# Driver_Board.net
KiCad netlist of a schematic drawn in EAGLE
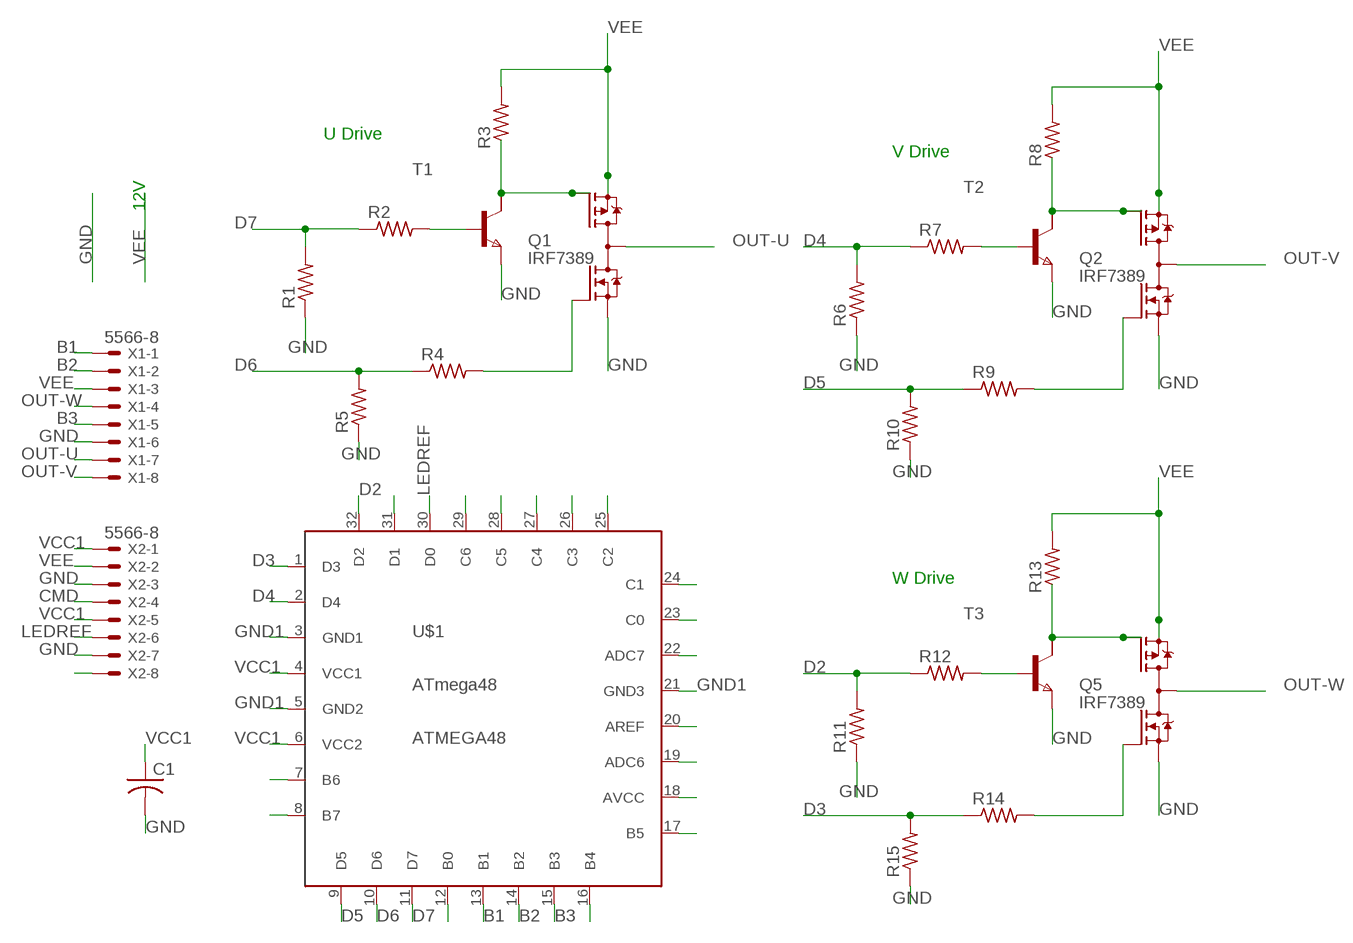
[diagram p0: schematic, sheet 1]

(export (version "E")
  (design (tool "Eeschema 10.0.6"))
  (components
    (comp (ref "C1")
      (value "C-USC1206")
      (footprint "eagle-import:C1206")
      (libsource (lib "eagle-import") (part "C-USC1206"))
    )
    (comp (ref "Q1")
      (value "IRF7389")
      (footprint "eagle-import:SO08-IRF")
      (libsource (lib "eagle-import") (part "IRF7389"))
    )
    (comp (ref "Q2")
      (value "IRF7389")
      (footprint "eagle-import:SO08-IRF")
      (libsource (lib "eagle-import") (part "IRF7389"))
    )
    (comp (ref "Q5")
      (value "IRF7389")
      (footprint "eagle-import:SO08-IRF")
      (libsource (lib "eagle-import") (part "IRF7389"))
    )
    (comp (ref "R1")
      (value "R-US_R1206")
      (footprint "eagle-import:R1206")
      (libsource (lib "eagle-import") (part "R-US_R1206"))
    )
    (comp (ref "R2")
      (value "R-US_R1206")
      (footprint "eagle-import:R1206")
      (libsource (lib "eagle-import") (part "R-US_R1206"))
    )
    (comp (ref "R3")
      (value "R-US_R1206")
      (footprint "eagle-import:R1206")
      (libsource (lib "eagle-import") (part "R-US_R1206"))
    )
    (comp (ref "R4")
      (value "R-US_R1206")
      (footprint "eagle-import:R1206")
      (libsource (lib "eagle-import") (part "R-US_R1206"))
    )
    (comp (ref "R5")
      (value "R-US_R1206")
      (footprint "eagle-import:R1206")
      (libsource (lib "eagle-import") (part "R-US_R1206"))
    )
    (comp (ref "R6")
      (value "R-US_R1206")
      (footprint "eagle-import:R1206")
      (libsource (lib "eagle-import") (part "R-US_R1206"))
    )
    (comp (ref "R7")
      (value "R-US_R1206")
      (footprint "eagle-import:R1206")
      (libsource (lib "eagle-import") (part "R-US_R1206"))
    )
    (comp (ref "R8")
      (value "R-US_R1206")
      (footprint "eagle-import:R1206")
      (libsource (lib "eagle-import") (part "R-US_R1206"))
    )
    (comp (ref "R9")
      (value "R-US_R1206")
      (footprint "eagle-import:R1206")
      (libsource (lib "eagle-import") (part "R-US_R1206"))
    )
    (comp (ref "R10")
      (value "R-US_R1206")
      (footprint "eagle-import:R1206")
      (libsource (lib "eagle-import") (part "R-US_R1206"))
    )
    (comp (ref "R11")
      (value "R-US_R1206")
      (footprint "eagle-import:R1206")
      (libsource (lib "eagle-import") (part "R-US_R1206"))
    )
    (comp (ref "R12")
      (value "R-US_R1206")
      (footprint "eagle-import:R1206")
      (libsource (lib "eagle-import") (part "R-US_R1206"))
    )
    (comp (ref "R13")
      (value "R-US_R1206")
      (footprint "eagle-import:R1206")
      (libsource (lib "eagle-import") (part "R-US_R1206"))
    )
    (comp (ref "R14")
      (value "R-US_R1206")
      (footprint "eagle-import:R1206")
      (libsource (lib "eagle-import") (part "R-US_R1206"))
    )
    (comp (ref "R15")
      (value "R-US_R1206")
      (footprint "eagle-import:R1206")
      (libsource (lib "eagle-import") (part "R-US_R1206"))
    )
    (comp (ref "T1")
      (value "NPNSOT223")
      (footprint "eagle-import:SOT223")
      (fields (field (name "MPN") "DJT4031N-13"))
      (libsource (lib "eagle-import") (part "NPNSOT223"))
    )
    (comp (ref "T2")
      (value "NPNSOT223")
      (footprint "eagle-import:SOT223")
      (fields (field (name "MPN") "DJT4031N-13"))
      (libsource (lib "eagle-import") (part "NPNSOT223"))
    )
    (comp (ref "T3")
      (value "NPNSOT223")
      (footprint "eagle-import:SOT223")
      (fields (field (name "MPN") "DJT4031N-13"))
      (libsource (lib "eagle-import") (part "NPNSOT223"))
    )
    (comp (ref "U$1")
      (value "ATMEGA48")
      (footprint "eagle-import:ATMEGA48")
      (libsource (lib "eagle-import") (part "ATMEGA48"))
    )
    (comp (ref "X1")
      (value "5566-8")
      (footprint "eagle-import:5566-8")
      (libsource (lib "eagle-import") (part "5566-8"))
    )
    (comp (ref "X2")
      (value "5566-8")
      (footprint "eagle-import:5566-8")
      (libsource (lib "eagle-import") (part "5566-8"))
    )
  )
  (nets
    (net (code "1") (name "/B1") (class "Default")
      (node (ref "U$1") (pin "13") (pinfunction "B1_13") (pintype "bidirectional"))
      (node (ref "X1") (pin "1") (pinfunction "S_1") (pintype "passive"))
    )
    (net (code "2") (name "/B2") (class "Default")
      (node (ref "U$1") (pin "14") (pinfunction "B2_14") (pintype "bidirectional"))
      (node (ref "X1") (pin "2") (pinfunction "S_2") (pintype "passive"))
    )
    (net (code "3") (name "/B3") (class "Default")
      (node (ref "U$1") (pin "15") (pinfunction "B3_15") (pintype "bidirectional"))
      (node (ref "X1") (pin "5") (pinfunction "S_5") (pintype "passive"))
    )
    (net (code "4") (name "/CMD") (class "Default")
      (node (ref "X2") (pin "4") (pinfunction "S_4") (pintype "passive"))
    )
    (net (code "5") (name "/D2") (class "Default")
      (node (ref "R11") (pin "2") (pinfunction "2_2") (pintype "passive"))
      (node (ref "R12") (pin "1") (pinfunction "1_1") (pintype "passive"))
      (node (ref "U$1") (pin "32") (pinfunction "D2_32") (pintype "bidirectional"))
    )
    (net (code "6") (name "/D3") (class "Default")
      (node (ref "R14") (pin "1") (pinfunction "1_1") (pintype "passive"))
      (node (ref "R15") (pin "2") (pinfunction "2_2") (pintype "passive"))
      (node (ref "U$1") (pin "1") (pinfunction "D3_1") (pintype "bidirectional"))
    )
    (net (code "7") (name "/D4") (class "Default")
      (node (ref "R6") (pin "2") (pinfunction "2_2") (pintype "passive"))
      (node (ref "R7") (pin "1") (pinfunction "1_1") (pintype "passive"))
      (node (ref "U$1") (pin "2") (pinfunction "D4_2") (pintype "bidirectional"))
    )
    (net (code "8") (name "/D5") (class "Default")
      (node (ref "R10") (pin "2") (pinfunction "2_2") (pintype "passive"))
      (node (ref "R9") (pin "1") (pinfunction "1_1") (pintype "passive"))
      (node (ref "U$1") (pin "9") (pinfunction "D5_9") (pintype "bidirectional"))
    )
    (net (code "9") (name "/D6") (class "Default")
      (node (ref "R4") (pin "1") (pinfunction "1_1") (pintype "passive"))
      (node (ref "R5") (pin "2") (pinfunction "2_2") (pintype "passive"))
      (node (ref "U$1") (pin "10") (pinfunction "D6_10") (pintype "bidirectional"))
    )
    (net (code "10") (name "/D7") (class "Default")
      (node (ref "R1") (pin "2") (pinfunction "2_2") (pintype "passive"))
      (node (ref "R2") (pin "1") (pinfunction "1_1") (pintype "passive"))
      (node (ref "U$1") (pin "11") (pinfunction "D7_11") (pintype "bidirectional"))
    )
    (net (code "11") (name "/GND") (class "Default")
      (node (ref "C1") (pin "2") (pinfunction "2_2") (pintype "passive"))
      (node (ref "Q1") (pin "1") (pinfunction "N-S_1") (pintype "passive"))
      (node (ref "Q2") (pin "1") (pinfunction "N-S_1") (pintype "passive"))
      (node (ref "Q5") (pin "1") (pinfunction "N-S_1") (pintype "passive"))
      (node (ref "R1") (pin "1") (pinfunction "1_1") (pintype "passive"))
      (node (ref "R10") (pin "1") (pinfunction "1_1") (pintype "passive"))
      (node (ref "R11") (pin "1") (pinfunction "1_1") (pintype "passive"))
      (node (ref "R15") (pin "1") (pinfunction "1_1") (pintype "passive"))
      (node (ref "R5") (pin "1") (pinfunction "1_1") (pintype "passive"))
      (node (ref "R6") (pin "1") (pinfunction "1_1") (pintype "passive"))
      (node (ref "T1") (pin "3") (pinfunction "E_3") (pintype "passive"))
      (node (ref "T2") (pin "3") (pinfunction "E_3") (pintype "passive"))
      (node (ref "T3") (pin "3") (pinfunction "E_3") (pintype "passive"))
      (node (ref "X1") (pin "6") (pinfunction "S_6") (pintype "passive"))
      (node (ref "X2") (pin "3") (pinfunction "S_3") (pintype "passive"))
      (node (ref "X2") (pin "7") (pinfunction "S_7") (pintype "passive"))
    )
    (net (code "12") (name "/GND1") (class "Default")
      (node (ref "U$1") (pin "21") (pinfunction "GND3_21") (pintype "bidirectional"))
      (node (ref "U$1") (pin "3") (pinfunction "GND1_3") (pintype "bidirectional"))
      (node (ref "U$1") (pin "5") (pinfunction "GND2_5") (pintype "bidirectional"))
    )
    (net (code "13") (name "/LEDREF") (class "Default")
      (node (ref "U$1") (pin "30") (pinfunction "D0_30") (pintype "bidirectional"))
      (node (ref "X2") (pin "6") (pinfunction "S_6") (pintype "passive"))
    )
    (net (code "14") (name "/OUT-U") (class "Default")
      (node (ref "Q1") (pin "5") (pinfunction "D_5") (pintype "passive"))
      (node (ref "Q1") (pin "6") (pinfunction "D_6") (pintype "passive"))
      (node (ref "Q1") (pin "7") (pinfunction "D_7") (pintype "passive"))
      (node (ref "Q1") (pin "8") (pinfunction "D_8") (pintype "passive"))
      (node (ref "X1") (pin "7") (pinfunction "S_7") (pintype "passive"))
    )
    (net (code "15") (name "/OUT-V") (class "Default")
      (node (ref "Q2") (pin "5") (pinfunction "D_5") (pintype "passive"))
      (node (ref "Q2") (pin "6") (pinfunction "D_6") (pintype "passive"))
      (node (ref "Q2") (pin "7") (pinfunction "D_7") (pintype "passive"))
      (node (ref "Q2") (pin "8") (pinfunction "D_8") (pintype "passive"))
      (node (ref "X1") (pin "8") (pinfunction "S_8") (pintype "passive"))
    )
    (net (code "16") (name "/OUT-W") (class "Default")
      (node (ref "Q5") (pin "5") (pinfunction "D_5") (pintype "passive"))
      (node (ref "Q5") (pin "6") (pinfunction "D_6") (pintype "passive"))
      (node (ref "Q5") (pin "7") (pinfunction "D_7") (pintype "passive"))
      (node (ref "Q5") (pin "8") (pinfunction "D_8") (pintype "passive"))
      (node (ref "X1") (pin "4") (pinfunction "S_4") (pintype "passive"))
    )
    (net (code "17") (name "/VCC1") (class "Default")
      (node (ref "C1") (pin "1") (pinfunction "1_1") (pintype "passive"))
      (node (ref "U$1") (pin "4") (pinfunction "VCC1_4") (pintype "bidirectional"))
      (node (ref "U$1") (pin "6") (pinfunction "VCC2_6") (pintype "bidirectional"))
      (node (ref "X2") (pin "1") (pinfunction "S_1") (pintype "passive"))
      (node (ref "X2") (pin "5") (pinfunction "S_5") (pintype "passive"))
    )
    (net (code "18") (name "/VEE") (class "Default")
      (node (ref "Q1") (pin "3") (pinfunction "P-S_3") (pintype "passive"))
      (node (ref "Q2") (pin "3") (pinfunction "P-S_3") (pintype "passive"))
      (node (ref "Q5") (pin "3") (pinfunction "P-S_3") (pintype "passive"))
      (node (ref "R13") (pin "2") (pinfunction "2_2") (pintype "passive"))
      (node (ref "R3") (pin "2") (pinfunction "2_2") (pintype "passive"))
      (node (ref "R8") (pin "2") (pinfunction "2_2") (pintype "passive"))
      (node (ref "X1") (pin "3") (pinfunction "S_3") (pintype "passive"))
      (node (ref "X2") (pin "2") (pinfunction "S_2") (pintype "passive"))
    )
    (net (code "19") (name "Net-(Q1-N-G)") (class "Default")
      (node (ref "Q1") (pin "2") (pinfunction "N-G_2") (pintype "passive"))
      (node (ref "R4") (pin "2") (pinfunction "2_2") (pintype "passive"))
    )
    (net (code "20") (name "Net-(Q1-P-G)") (class "Default")
      (node (ref "Q1") (pin "4") (pinfunction "P-G_4") (pintype "passive"))
      (node (ref "T1") (pin "2") (pinfunction "C1_2") (pintype "passive"))
    )
    (net (code "21") (name "Net-(Q2-N-G)") (class "Default")
      (node (ref "Q2") (pin "2") (pinfunction "N-G_2") (pintype "passive"))
      (node (ref "R9") (pin "2") (pinfunction "2_2") (pintype "passive"))
    )
    (net (code "22") (name "Net-(Q2-P-G)") (class "Default")
      (node (ref "Q2") (pin "4") (pinfunction "P-G_4") (pintype "passive"))
      (node (ref "T2") (pin "2") (pinfunction "C1_2") (pintype "passive"))
    )
    (net (code "23") (name "Net-(Q5-N-G)") (class "Default")
      (node (ref "Q5") (pin "2") (pinfunction "N-G_2") (pintype "passive"))
      (node (ref "R14") (pin "2") (pinfunction "2_2") (pintype "passive"))
    )
    (net (code "24") (name "Net-(Q5-P-G)") (class "Default")
      (node (ref "Q5") (pin "4") (pinfunction "P-G_4") (pintype "passive"))
      (node (ref "T3") (pin "2") (pinfunction "C1_2") (pintype "passive"))
    )
    (net (code "25") (name "Net-(T1-B)") (class "Default")
      (node (ref "R2") (pin "2") (pinfunction "2_2") (pintype "passive"))
      (node (ref "T1") (pin "1") (pinfunction "B_1") (pintype "passive"))
    )
    (net (code "26") (name "Net-(T2-B)") (class "Default")
      (node (ref "R7") (pin "2") (pinfunction "2_2") (pintype "passive"))
      (node (ref "T2") (pin "1") (pinfunction "B_1") (pintype "passive"))
    )
    (net (code "27") (name "Net-(T3-B)") (class "Default")
      (node (ref "R12") (pin "2") (pinfunction "2_2") (pintype "passive"))
      (node (ref "T3") (pin "1") (pinfunction "B_1") (pintype "passive"))
    )
    (net (code "28") (name "unconnected-(R3-Pad1)") (class "Default")
      (node (ref "R3") (pin "1") (pinfunction "1_1") (pintype "passive"))
    )
    (net (code "29") (name "unconnected-(R8-Pad1)") (class "Default")
      (node (ref "R8") (pin "1") (pinfunction "1_1") (pintype "passive"))
    )
    (net (code "30") (name "unconnected-(R13-Pad1)") (class "Default")
      (node (ref "R13") (pin "1") (pinfunction "1_1") (pintype "passive"))
    )
    (net (code "31") (name "unconnected-(T1-C2-Pad4)") (class "Default")
      (node (ref "T1") (pin "4") (pinfunction "C2_4") (pintype "passive"))
    )
    (net (code "32") (name "unconnected-(T2-C2-Pad4)") (class "Default")
      (node (ref "T2") (pin "4") (pinfunction "C2_4") (pintype "passive"))
    )
    (net (code "33") (name "unconnected-(T3-C2-Pad4)") (class "Default")
      (node (ref "T3") (pin "4") (pinfunction "C2_4") (pintype "passive"))
    )
    (net (code "34") (name "unconnected-(U$1-ADC6-Pad19)") (class "Default")
      (node (ref "U$1") (pin "19") (pinfunction "ADC6_19") (pintype "bidirectional"))
    )
    (net (code "35") (name "unconnected-(U$1-ADC7-Pad22)") (class "Default")
      (node (ref "U$1") (pin "22") (pinfunction "ADC7_22") (pintype "bidirectional"))
    )
    (net (code "36") (name "unconnected-(U$1-AREF-Pad20)") (class "Default")
      (node (ref "U$1") (pin "20") (pinfunction "AREF_20") (pintype "bidirectional"))
    )
    (net (code "37") (name "unconnected-(U$1-AVCC-Pad18)") (class "Default")
      (node (ref "U$1") (pin "18") (pinfunction "AVCC_18") (pintype "bidirectional"))
    )
    (net (code "38") (name "unconnected-(U$1-B0-Pad12)") (class "Default")
      (node (ref "U$1") (pin "12") (pinfunction "B0_12") (pintype "bidirectional"))
    )
    (net (code "39") (name "unconnected-(U$1-B4-Pad16)") (class "Default")
      (node (ref "U$1") (pin "16") (pinfunction "B4_16") (pintype "bidirectional"))
    )
    (net (code "40") (name "unconnected-(U$1-B5-Pad17)") (class "Default")
      (node (ref "U$1") (pin "17") (pinfunction "B5_17") (pintype "bidirectional"))
    )
    (net (code "41") (name "unconnected-(U$1-B6-Pad7)") (class "Default")
      (node (ref "U$1") (pin "7") (pinfunction "B6_7") (pintype "bidirectional"))
    )
    (net (code "42") (name "unconnected-(U$1-B7-Pad8)") (class "Default")
      (node (ref "U$1") (pin "8") (pinfunction "B7_8") (pintype "bidirectional"))
    )
    (net (code "43") (name "unconnected-(U$1-C0-Pad23)") (class "Default")
      (node (ref "U$1") (pin "23") (pinfunction "C0_23") (pintype "bidirectional"))
    )
    (net (code "44") (name "unconnected-(U$1-C1-Pad24)") (class "Default")
      (node (ref "U$1") (pin "24") (pinfunction "C1_24") (pintype "bidirectional"))
    )
    (net (code "45") (name "unconnected-(U$1-C2-Pad25)") (class "Default")
      (node (ref "U$1") (pin "25") (pinfunction "C2_25") (pintype "bidirectional"))
    )
    (net (code "46") (name "unconnected-(U$1-C3-Pad26)") (class "Default")
      (node (ref "U$1") (pin "26") (pinfunction "C3_26") (pintype "bidirectional"))
    )
    (net (code "47") (name "unconnected-(U$1-C4-Pad27)") (class "Default")
      (node (ref "U$1") (pin "27") (pinfunction "C4_27") (pintype "bidirectional"))
    )
    (net (code "48") (name "unconnected-(U$1-C5-Pad28)") (class "Default")
      (node (ref "U$1") (pin "28") (pinfunction "C5_28") (pintype "bidirectional"))
    )
    (net (code "49") (name "unconnected-(U$1-C6-Pad29)") (class "Default")
      (node (ref "U$1") (pin "29") (pinfunction "C6_29") (pintype "bidirectional"))
    )
    (net (code "50") (name "unconnected-(U$1-D1-Pad31)") (class "Default")
      (node (ref "U$1") (pin "31") (pinfunction "D1_31") (pintype "bidirectional"))
    )
    (net (code "51") (name "unconnected-(X2H-S-Pad8)") (class "Default")
      (node (ref "X2") (pin "8") (pinfunction "S_8") (pintype "passive"))
    )
  )
)
